# gt-jtx-m32-ver1_0.net
KiCad netlist of a schematic drawn in EAGLE
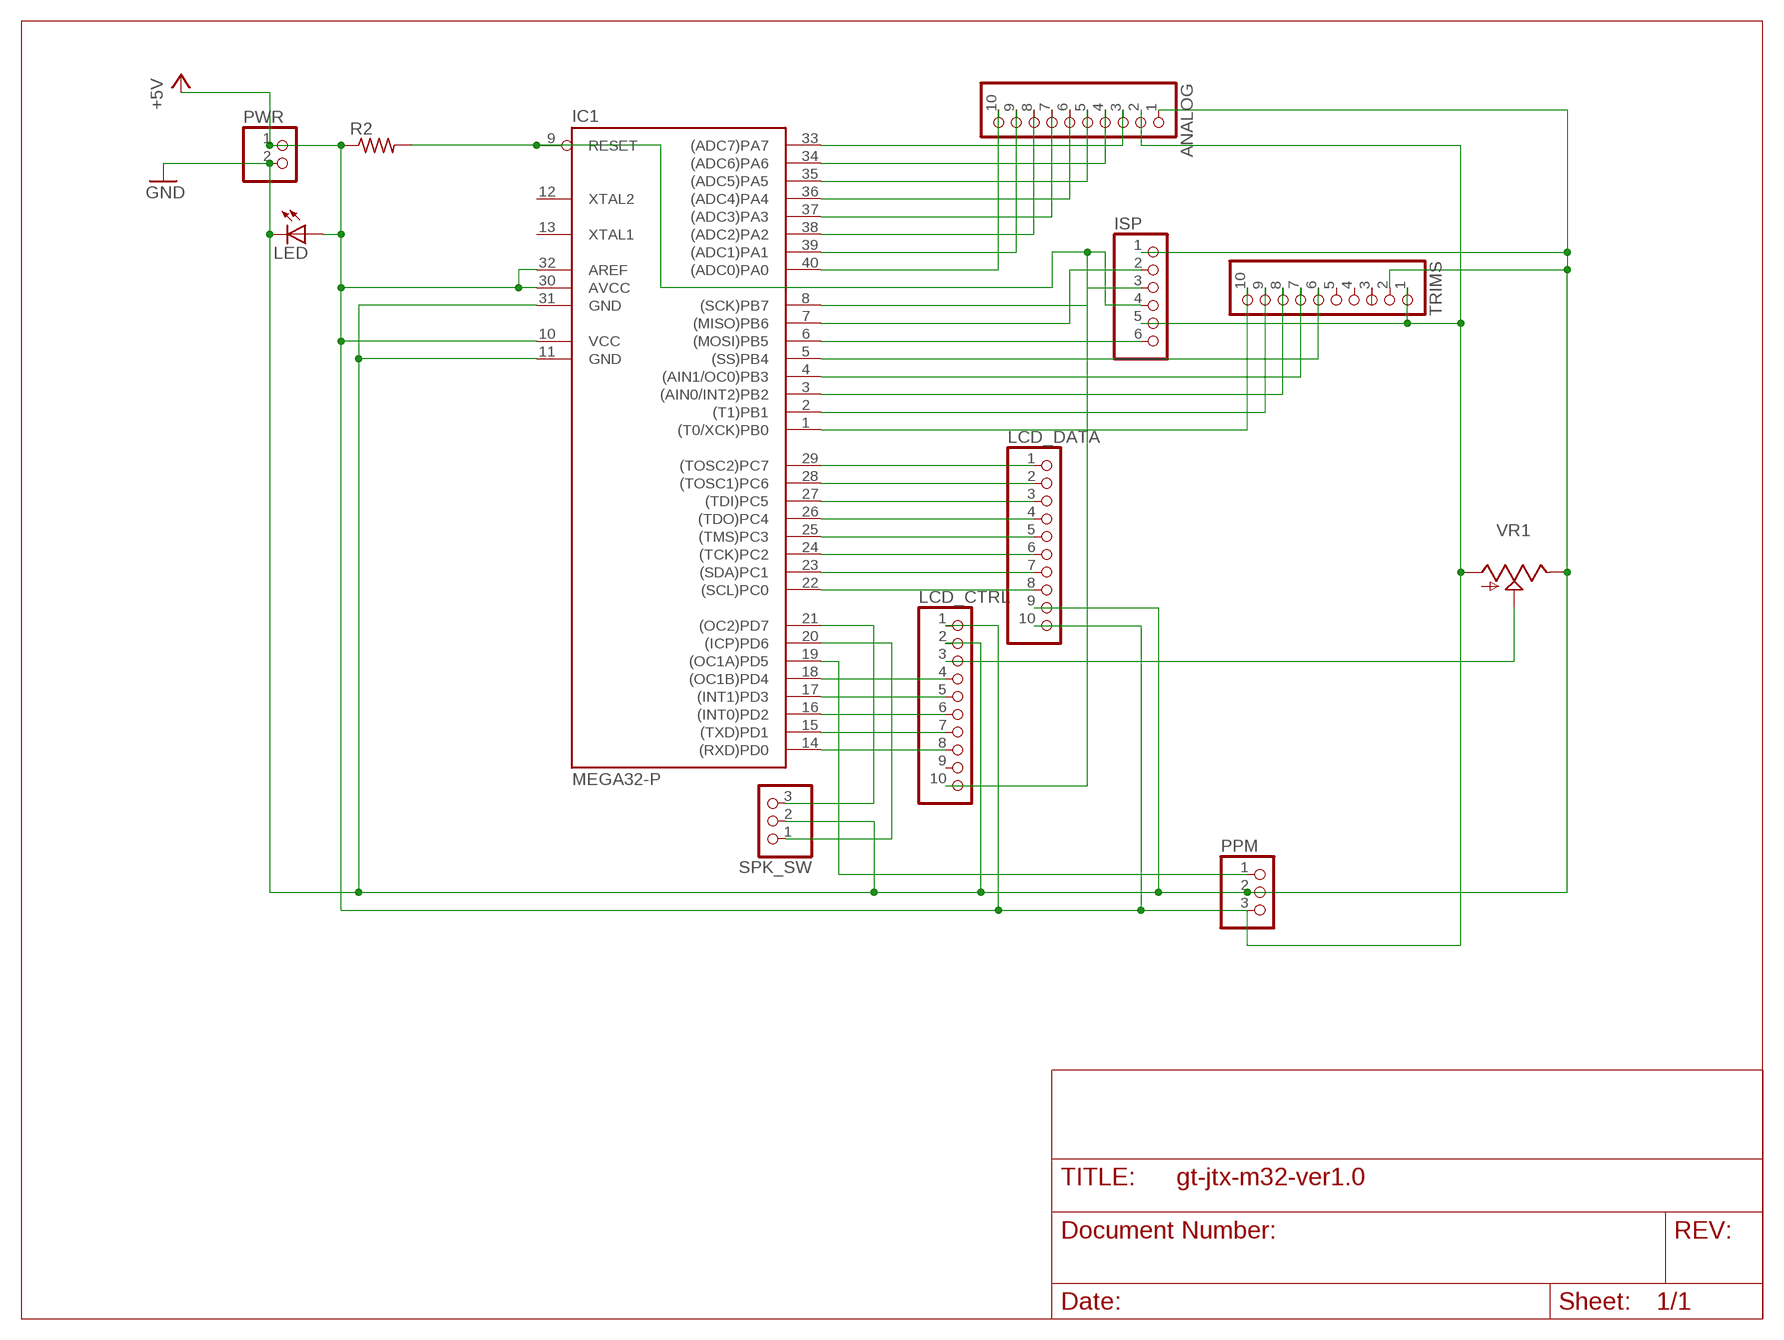
[diagram p0: schematic, sheet 1]

(export (version "E")
  (design (tool "Eeschema 10.0.6"))
  (components
    (comp (ref "ANALOG")
      (value "PINHD-1X10")
      (footprint "eagle-import:1X10")
      (libsource (lib "eagle-import") (part "PINHD-1X10"))
    )
    (comp (ref "IC1")
      (value "MEGA32-P")
      (footprint "eagle-import:DIL40")
      (fields (field (name "MPN") "ATMEGA32-16PU"))
      (libsource (lib "eagle-import") (part "MEGA32-P"))
    )
    (comp (ref "ISP")
      (value "PINHD-1X6")
      (footprint "eagle-import:1X06")
      (libsource (lib "eagle-import") (part "PINHD-1X6"))
    )
    (comp (ref "LCD_CTRL")
      (value "PINHD-1X10")
      (footprint "eagle-import:1X10")
      (libsource (lib "eagle-import") (part "PINHD-1X10"))
    )
    (comp (ref "LCD_DATA")
      (value "PINHD-1X10")
      (footprint "eagle-import:1X10")
      (libsource (lib "eagle-import") (part "PINHD-1X10"))
    )
    (comp (ref "LED")
      (value "LED5MM")
      (footprint "eagle-import:LED5MM")
      (libsource (lib "eagle-import") (part "LED5MM"))
    )
    (comp (ref "PPM")
      (value "PINHD-1X3")
      (footprint "eagle-import:1X03")
      (libsource (lib "eagle-import") (part "PINHD-1X3"))
    )
    (comp (ref "PWR")
      (value "PINHD-1X2")
      (footprint "eagle-import:1X02")
      (libsource (lib "eagle-import") (part "PINHD-1X2"))
    )
    (comp (ref "R2")
      (value "R-US_0204/2V")
      (footprint "eagle-import:0204V")
      (libsource (lib "eagle-import") (part "R-US_0204/2V"))
    )
    (comp (ref "SPK_SW")
      (value "PINHD-1X3")
      (footprint "eagle-import:1X03")
      (libsource (lib "eagle-import") (part "PINHD-1X3"))
    )
    (comp (ref "TRIMS")
      (value "PINHD-1X10")
      (footprint "eagle-import:1X10")
      (libsource (lib "eagle-import") (part "PINHD-1X10"))
    )
    (comp (ref "VR1")
      (value "TRIM_US-CA6V")
      (footprint "eagle-import:CA6V")
      (libsource (lib "eagle-import") (part "TRIM_US-CA6V"))
    )
  )
  (nets
    (net (code "1") (name "+5V") (class "Default")
      (node (ref "ANALOG") (pin "2") (pinfunction "2_2") (pintype "passive"))
      (node (ref "IC1") (pin "10") (pinfunction "VCC_10") (pintype "power_in"))
      (node (ref "IC1") (pin "30") (pinfunction "AVCC_30") (pintype "power_in"))
      (node (ref "IC1") (pin "32") (pinfunction "AREF_32") (pintype "passive"))
      (node (ref "ISP") (pin "5") (pinfunction "5_5") (pintype "passive"))
      (node (ref "LCD_CTRL") (pin "1") (pinfunction "1_1") (pintype "passive"))
      (node (ref "LCD_DATA") (pin "10") (pinfunction "10_10") (pintype "passive"))
      (node (ref "LED") (pin "A") (pinfunction "A_A") (pintype "passive"))
      (node (ref "PPM") (pin "3") (pinfunction "3_3") (pintype "passive"))
      (node (ref "PWR") (pin "1") (pinfunction "1_1") (pintype "passive"))
      (node (ref "R2") (pin "1") (pinfunction "1_1") (pintype "passive"))
      (node (ref "TRIMS") (pin "1") (pinfunction "1_1") (pintype "passive"))
      (node (ref "VR1") (pin "A") (pinfunction "A_A") (pintype "passive"))
    )
    (net (code "2") (name "GND") (class "Default")
      (node (ref "ANALOG") (pin "1") (pinfunction "1_1") (pintype "passive"))
      (node (ref "IC1") (pin "11") (pinfunction "GND_11") (pintype "power_in"))
      (node (ref "IC1") (pin "31") (pinfunction "GND_31") (pintype "power_in"))
      (node (ref "ISP") (pin "1") (pinfunction "1_1") (pintype "passive"))
      (node (ref "LCD_CTRL") (pin "2") (pinfunction "2_2") (pintype "passive"))
      (node (ref "LCD_DATA") (pin "9") (pinfunction "9_9") (pintype "passive"))
      (node (ref "LED") (pin "K") (pinfunction "C_K") (pintype "passive"))
      (node (ref "PPM") (pin "2") (pinfunction "2_2") (pintype "passive"))
      (node (ref "PWR") (pin "2") (pinfunction "2_2") (pintype "passive"))
      (node (ref "SPK_SW") (pin "2") (pinfunction "2_2") (pintype "passive"))
      (node (ref "TRIMS") (pin "2") (pinfunction "2_2") (pintype "passive"))
      (node (ref "VR1") (pin "E") (pinfunction "E_E") (pintype "passive"))
    )
    (net (code "3") (name "Net-(IC1-(ADC0)PA0)") (class "Default")
      (node (ref "ANALOG") (pin "10") (pinfunction "10_10") (pintype "passive"))
      (node (ref "IC1") (pin "40") (pinfunction "(ADC0)PA0_40") (pintype "bidirectional"))
    )
    (net (code "4") (name "Net-(IC1-(ADC1)PA1)") (class "Default")
      (node (ref "ANALOG") (pin "9") (pinfunction "9_9") (pintype "passive"))
      (node (ref "IC1") (pin "39") (pinfunction "(ADC1)PA1_39") (pintype "bidirectional"))
    )
    (net (code "5") (name "Net-(IC1-(ADC2)PA2)") (class "Default")
      (node (ref "ANALOG") (pin "8") (pinfunction "8_8") (pintype "passive"))
      (node (ref "IC1") (pin "38") (pinfunction "(ADC2)PA2_38") (pintype "bidirectional"))
    )
    (net (code "6") (name "Net-(IC1-(ADC3)PA3)") (class "Default")
      (node (ref "ANALOG") (pin "7") (pinfunction "7_7") (pintype "passive"))
      (node (ref "IC1") (pin "37") (pinfunction "(ADC3)PA3_37") (pintype "bidirectional"))
    )
    (net (code "7") (name "Net-(IC1-(ADC4)PA4)") (class "Default")
      (node (ref "ANALOG") (pin "6") (pinfunction "6_6") (pintype "passive"))
      (node (ref "IC1") (pin "36") (pinfunction "(ADC4)PA4_36") (pintype "bidirectional"))
    )
    (net (code "8") (name "Net-(IC1-(ADC5)PA5)") (class "Default")
      (node (ref "ANALOG") (pin "5") (pinfunction "5_5") (pintype "passive"))
      (node (ref "IC1") (pin "35") (pinfunction "(ADC5)PA5_35") (pintype "bidirectional"))
    )
    (net (code "9") (name "Net-(IC1-(ADC6)PA6)") (class "Default")
      (node (ref "ANALOG") (pin "4") (pinfunction "4_4") (pintype "passive"))
      (node (ref "IC1") (pin "34") (pinfunction "(ADC6)PA6_34") (pintype "bidirectional"))
    )
    (net (code "10") (name "Net-(IC1-(ADC7)PA7)") (class "Default")
      (node (ref "ANALOG") (pin "3") (pinfunction "3_3") (pintype "passive"))
      (node (ref "IC1") (pin "33") (pinfunction "(ADC7)PA7_33") (pintype "bidirectional"))
    )
    (net (code "11") (name "Net-(IC1-(AIN0{slash}INT2)PB2)") (class "Default")
      (node (ref "IC1") (pin "3") (pinfunction "(AIN0/INT2)PB2_3") (pintype "bidirectional"))
      (node (ref "TRIMS") (pin "8") (pinfunction "8_8") (pintype "passive"))
    )
    (net (code "12") (name "Net-(IC1-(AIN1{slash}OC0)PB3)") (class "Default")
      (node (ref "IC1") (pin "4") (pinfunction "(AIN1/OC0)PB3_4") (pintype "bidirectional"))
      (node (ref "TRIMS") (pin "7") (pinfunction "7_7") (pintype "passive"))
    )
    (net (code "13") (name "Net-(IC1-(ICP)PD6)") (class "Default")
      (node (ref "IC1") (pin "20") (pinfunction "(ICP)PD6_20") (pintype "bidirectional"))
      (node (ref "SPK_SW") (pin "1") (pinfunction "1_1") (pintype "passive"))
    )
    (net (code "14") (name "Net-(IC1-(INT0)PD2)") (class "Default")
      (node (ref "IC1") (pin "16") (pinfunction "(INT0)PD2_16") (pintype "bidirectional"))
      (node (ref "LCD_CTRL") (pin "6") (pinfunction "6_6") (pintype "passive"))
    )
    (net (code "15") (name "Net-(IC1-(INT1)PD3)") (class "Default")
      (node (ref "IC1") (pin "17") (pinfunction "(INT1)PD3_17") (pintype "bidirectional"))
      (node (ref "LCD_CTRL") (pin "5") (pinfunction "5_5") (pintype "passive"))
    )
    (net (code "16") (name "Net-(IC1-(MISO)PB6)") (class "Default")
      (node (ref "IC1") (pin "7") (pinfunction "(MISO)PB6_7") (pintype "bidirectional"))
      (node (ref "ISP") (pin "2") (pinfunction "2_2") (pintype "passive"))
    )
    (net (code "17") (name "Net-(IC1-(MOSI)PB5)") (class "Default")
      (node (ref "IC1") (pin "6") (pinfunction "(MOSI)PB5_6") (pintype "bidirectional"))
      (node (ref "ISP") (pin "6") (pinfunction "6_6") (pintype "passive"))
    )
    (net (code "18") (name "Net-(IC1-(OC1A)PD5)") (class "Default")
      (node (ref "IC1") (pin "19") (pinfunction "(OC1A)PD5_19") (pintype "bidirectional"))
      (node (ref "PPM") (pin "1") (pinfunction "1_1") (pintype "passive"))
    )
    (net (code "19") (name "Net-(IC1-(OC1B)PD4)") (class "Default")
      (node (ref "IC1") (pin "18") (pinfunction "(OC1B)PD4_18") (pintype "bidirectional"))
      (node (ref "LCD_CTRL") (pin "4") (pinfunction "4_4") (pintype "passive"))
    )
    (net (code "20") (name "Net-(IC1-(OC2)PD7)") (class "Default")
      (node (ref "IC1") (pin "21") (pinfunction "(OC2)PD7_21") (pintype "bidirectional"))
      (node (ref "SPK_SW") (pin "3") (pinfunction "3_3") (pintype "passive"))
    )
    (net (code "21") (name "Net-(IC1-(RXD)PD0)") (class "Default")
      (node (ref "IC1") (pin "14") (pinfunction "(RXD)PD0_14") (pintype "bidirectional"))
      (node (ref "LCD_CTRL") (pin "8") (pinfunction "8_8") (pintype "passive"))
    )
    (net (code "22") (name "Net-(IC1-(SCK)PB7)") (class "Default")
      (node (ref "IC1") (pin "8") (pinfunction "(SCK)PB7_8") (pintype "bidirectional"))
      (node (ref "ISP") (pin "3") (pinfunction "3_3") (pintype "passive"))
    )
    (net (code "23") (name "Net-(IC1-(SCL)PC0)") (class "Default")
      (node (ref "IC1") (pin "22") (pinfunction "(SCL)PC0_22") (pintype "bidirectional"))
      (node (ref "LCD_DATA") (pin "8") (pinfunction "8_8") (pintype "passive"))
    )
    (net (code "24") (name "Net-(IC1-(SDA)PC1)") (class "Default")
      (node (ref "IC1") (pin "23") (pinfunction "(SDA)PC1_23") (pintype "bidirectional"))
      (node (ref "LCD_DATA") (pin "7") (pinfunction "7_7") (pintype "passive"))
    )
    (net (code "25") (name "Net-(IC1-(SS)PB4)") (class "Default")
      (node (ref "IC1") (pin "5") (pinfunction "(SS)PB4_5") (pintype "bidirectional"))
      (node (ref "TRIMS") (pin "6") (pinfunction "6_6") (pintype "passive"))
    )
    (net (code "26") (name "Net-(IC1-(T0{slash}XCK)PB0)") (class "Default")
      (node (ref "IC1") (pin "1") (pinfunction "(T0/XCK)PB0_1") (pintype "bidirectional"))
      (node (ref "TRIMS") (pin "10") (pinfunction "10_10") (pintype "passive"))
    )
    (net (code "27") (name "Net-(IC1-(T1)PB1)") (class "Default")
      (node (ref "IC1") (pin "2") (pinfunction "(T1)PB1_2") (pintype "bidirectional"))
      (node (ref "TRIMS") (pin "9") (pinfunction "9_9") (pintype "passive"))
    )
    (net (code "28") (name "Net-(IC1-(TCK)PC2)") (class "Default")
      (node (ref "IC1") (pin "24") (pinfunction "(TCK)PC2_24") (pintype "bidirectional"))
      (node (ref "LCD_DATA") (pin "6") (pinfunction "6_6") (pintype "passive"))
    )
    (net (code "29") (name "Net-(IC1-(TDI)PC5)") (class "Default")
      (node (ref "IC1") (pin "27") (pinfunction "(TDI)PC5_27") (pintype "bidirectional"))
      (node (ref "LCD_DATA") (pin "3") (pinfunction "3_3") (pintype "passive"))
    )
    (net (code "30") (name "Net-(IC1-(TDO)PC4)") (class "Default")
      (node (ref "IC1") (pin "26") (pinfunction "(TDO)PC4_26") (pintype "bidirectional"))
      (node (ref "LCD_DATA") (pin "4") (pinfunction "4_4") (pintype "passive"))
    )
    (net (code "31") (name "Net-(IC1-(TMS)PC3)") (class "Default")
      (node (ref "IC1") (pin "25") (pinfunction "(TMS)PC3_25") (pintype "bidirectional"))
      (node (ref "LCD_DATA") (pin "5") (pinfunction "5_5") (pintype "passive"))
    )
    (net (code "32") (name "Net-(IC1-(TOSC1)PC6)") (class "Default")
      (node (ref "IC1") (pin "28") (pinfunction "(TOSC1)PC6_28") (pintype "bidirectional"))
      (node (ref "LCD_DATA") (pin "2") (pinfunction "2_2") (pintype "passive"))
    )
    (net (code "33") (name "Net-(IC1-(TOSC2)PC7)") (class "Default")
      (node (ref "IC1") (pin "29") (pinfunction "(TOSC2)PC7_29") (pintype "bidirectional"))
      (node (ref "LCD_DATA") (pin "1") (pinfunction "1_1") (pintype "passive"))
    )
    (net (code "34") (name "Net-(IC1-(TXD)PD1)") (class "Default")
      (node (ref "IC1") (pin "15") (pinfunction "(TXD)PD1_15") (pintype "bidirectional"))
      (node (ref "LCD_CTRL") (pin "7") (pinfunction "7_7") (pintype "passive"))
    )
    (net (code "35") (name "Net-(IC1-RESET)") (class "Default")
      (node (ref "IC1") (pin "9") (pinfunction "RESET_9") (pintype "input"))
      (node (ref "ISP") (pin "4") (pinfunction "4_4") (pintype "passive"))
      (node (ref "LCD_CTRL") (pin "10") (pinfunction "10_10") (pintype "passive"))
      (node (ref "R2") (pin "2") (pinfunction "2_2") (pintype "passive"))
    )
    (net (code "36") (name "Net-(LCD_CTRL-Pad3)") (class "Default")
      (node (ref "LCD_CTRL") (pin "3") (pinfunction "3_3") (pintype "passive"))
      (node (ref "VR1") (pin "S") (pinfunction "S_S") (pintype "passive"))
    )
    (net (code "37") (name "unconnected-(IC1-XTAL1-Pad13)") (class "Default")
      (node (ref "IC1") (pin "13") (pinfunction "XTAL1_13") (pintype "bidirectional"))
    )
    (net (code "38") (name "unconnected-(IC1-XTAL2-Pad12)") (class "Default")
      (node (ref "IC1") (pin "12") (pinfunction "XTAL2_12") (pintype "bidirectional"))
    )
    (net (code "39") (name "unconnected-(LCD_CTRL-Pad9)") (class "Default")
      (node (ref "LCD_CTRL") (pin "9") (pinfunction "9_9") (pintype "passive"))
    )
    (net (code "40") (name "unconnected-(TRIMS-Pad3)") (class "Default")
      (node (ref "TRIMS") (pin "3") (pinfunction "3_3") (pintype "passive"))
    )
    (net (code "41") (name "unconnected-(TRIMS-Pad4)") (class "Default")
      (node (ref "TRIMS") (pin "4") (pinfunction "4_4") (pintype "passive"))
    )
    (net (code "42") (name "unconnected-(TRIMS-Pad5)") (class "Default")
      (node (ref "TRIMS") (pin "5") (pinfunction "5_5") (pintype "passive"))
    )
  )
)
